# Single_cell_module.net
KiCad netlist of a schematic drawn in Altium Designer
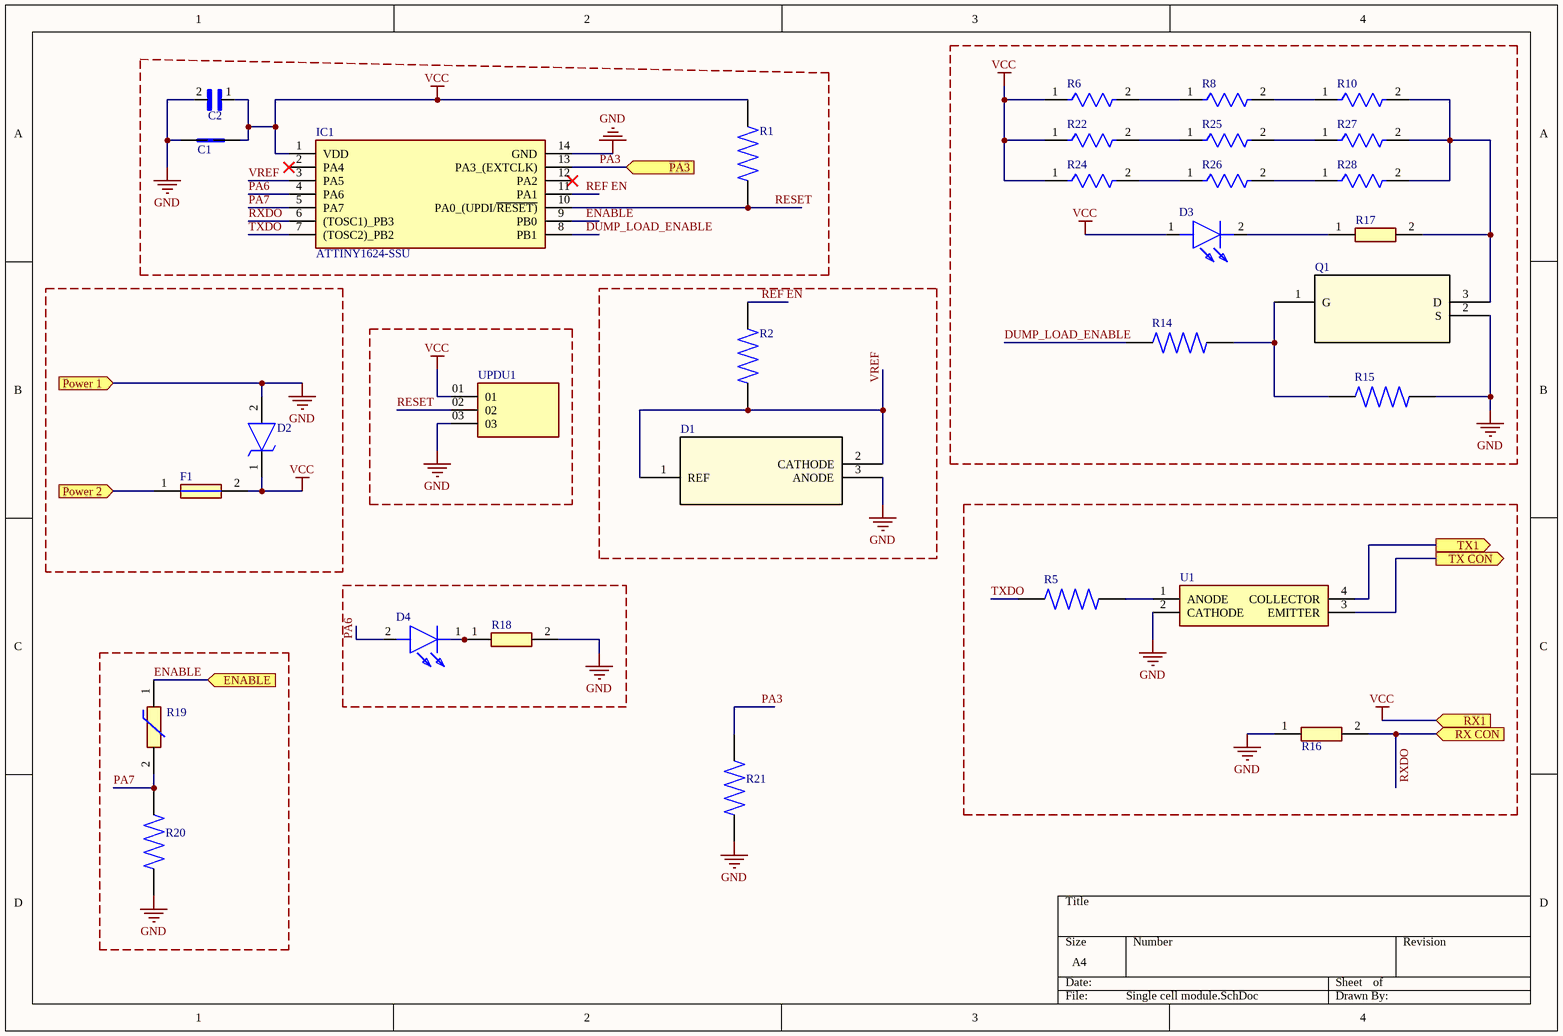
[diagram p0: Single cell module.SchDoc]

(export (version "E")
  (design (tool "Eeschema 10.0.6"))
  (components
    (comp (ref "C1")
      (value "CC0805KRX7R9BB104")
      (footprint "CAPC2012X70")
      (description "0.1ÂµF Â±10% 50V Ceramic Capacitor X7R 0805 _2012 Metric_")
      (fields (field (name "MF") "Yageo"))
      (libsource (lib "CC0805KRX7R9BB104") (part "CC0805KRX7R9BB104"))
    )
    (comp (ref "C2")
      (value "CL21A106KAYNNNE")
      (footprint "CAPC2012X135N")
      (description "10ÂµF Â±10% 25V Ceramic Capacitor X5R 0805 (2012 Metric)")
      (fields (field (name "MF") "Samsung") (field (name "DIGI-KEY_PART_NUMBER") "1276-2891-1-ND"))
      (libsource (lib "CL21A106KAYNNNE") (part "CL21A106KAYNNNE"))
    )
    (comp (ref "D1")
      (value "AZ432ANTR-E1")
      (footprint "SOT-23_DIO")
      (description "No Description Available")
      (libsource (lib "AZ432ANTR-E1") (part "AZ432ANTR-E1"))
    )
    (comp (ref "D2")
      (value "SM6T6V8A")
      (footprint "SamacSys:DIOM5436X265N")
      (description "TVS Diode (Uni-directional)")
      (fields (field (name "MOUSER PART NUMBER") "511-SM6T6V8A"))
      (libsource (lib "*") (part "SM6T6V8A"))
    )
    (comp (ref "D3")
      (value "598-2105-107F")
      (footprint "SamacSys:5982105107F")
      (description "LED")
      (libsource (lib "*") (part "598-2105-107F"))
    )
    (comp (ref "D4")
      (value "19-217_GHC-YR1S2_3T")
      (footprint "SamacSys:LEDC1608X50N")
      (description "LED")
      (fields
        (field (name "MANUFACTURER_PART_NUMBER") "19-217/GHC-YR1S2/3T")
        (field (name "MOUSER PART NUMBER") "638-19217GHCYR1S23T")
      )
      (libsource (lib "*") (part "19-217_GHC-YR1S2_3T"))
    )
    (comp (ref "F1")
      (value "MF-MSMF150-2")
      (footprint "SamacSys:FUSC4632X85N")
      (description "Fuse")
      (fields (field (name "MOUSER PART NUMBER") "652-MF-MSMF150-2"))
      (libsource (lib "*") (part "MF-MSMF150-2"))
    )
    (comp (ref "IC1")
      (value "ATTINY1624-SSU")
      (footprint "SamacSys:SOIC127P600X175-14N")
      (description "Integrated Circuit")
      (fields (field (name "MOUSER PART NUMBER") "556-ATTINY1624-SSU"))
      (libsource (lib "*") (part "ATTINY1624-SSU"))
    )
    (comp (ref "Q1")
      (value "AO3400A")
      (footprint "SOT-23-3L_AOS")
      (description "No Description Available")
      (libsource (lib "AO3400A") (part "AO3400A"))
    )
    (comp (ref "R1")
      (value "ERA6ARW104V")
      (footprint "RES_ERA6ARW104V")
      (libsource (lib "ERA6ARW104V") (part "ERA6ARW104V"))
    )
    (comp (ref "R2")
      (value "ERJU06J102V")
      (footprint "RES_ERJU06J102V")
      (libsource (lib "ERJU06J102V") (part "ERJU06J102V"))
    )
    (comp (ref "R5")
      (value "ERJ6ENF1800V")
      (footprint "RES_ERJ6ENF1800V")
      (libsource (lib "ERJ6ENF1800V") (part "ERJ6ENF1800V"))
    )
    (comp (ref "R6")
      (value "RC2010JK-070RL")
      (footprint "FP-RC2010-0_65-IPC_C")
      (description "RES SMD 0 OHM JUMPER 3/4W 2010")
      (fields (field (name "TOLERANCE") "5%"))
      (libsource (lib "Altium Content Vault") (part "1029c3af85768c4190bb7ad29bc67b5"))
    )
    (comp (ref "R8")
      (value "RC2010JK-070RL")
      (footprint "FP-RC2010-0_65-IPC_C")
      (description "RES SMD 0 OHM JUMPER 3/4W 2010")
      (fields (field (name "TOLERANCE") "5%"))
      (libsource (lib "Altium Content Vault") (part "1029c3af85768c4190bb7ad29bc67b5"))
    )
    (comp (ref "R10")
      (value "RC2010JK-070RL")
      (footprint "FP-RC2010-0_65-IPC_C")
      (description "RES SMD 0 OHM JUMPER 3/4W 2010")
      (fields (field (name "TOLERANCE") "5%"))
      (libsource (lib "Altium Content Vault") (part "1029c3af85768c4190bb7ad29bc67b5"))
    )
    (comp (ref "R14")
      (value "RT1206DRD07510RL")
      (footprint "RESC3116X65N")
      (description "RES SMD 510 OHM 0.5% 1/8W 1206")
      (libsource (lib "RT1206DRD07510RL") (part "RT1206DRD07510RL"))
    )
    (comp (ref "R15")
      (value "ERJP06D1002V")
      (footprint "RES_ERJP06D1002V")
      (libsource (lib "ERJP06D1002V") (part "ERJP06D1002V"))
    )
    (comp (ref "R16")
      (value "0805W8F2201T5E")
      (footprint "SamacSys:RESC2013X65N")
      (description "Resistor")
      (fields (field (name "MOUSER PART NUMBER") "303-0805W8F2201T5E"))
      (libsource (lib "*") (part "0805W8F2201T5E"))
    )
    (comp (ref "R17")
      (value "0805W8F2201T5E")
      (footprint "SamacSys:RESC2013X65N")
      (description "Resistor")
      (fields (field (name "MOUSER PART NUMBER") "303-0805W8F2201T5E"))
      (libsource (lib "*") (part "0805W8F2201T5E"))
    )
    (comp (ref "R18")
      (value "0805W8F2201T5E")
      (footprint "SamacSys:RESC2013X65N")
      (description "Resistor")
      (fields (field (name "MOUSER PART NUMBER") "303-0805W8F2201T5E"))
      (libsource (lib "*") (part "0805W8F2201T5E"))
    )
    (comp (ref "R19")
      (value "NTCS0805E3104GMT")
      (footprint "SamacSys:THRMC2012X95N")
      (description "Thermistor")
      (fields (field (name "MOUSER PART NUMBER") "594-NTCS0805E3104GMT"))
      (libsource (lib "*") (part "NTCS0805E3104GMT"))
    )
    (comp (ref "R20")
      (value "ERJP06D1002V")
      (footprint "RES_ERJP06D1002V")
      (libsource (lib "ERJP06D1002V") (part "ERJP06D1002V"))
    )
    (comp (ref "R21")
      (value "ERJP06D1002V")
      (footprint "RES_ERJP06D1002V")
      (libsource (lib "ERJP06D1002V") (part "ERJP06D1002V"))
    )
    (comp (ref "R22")
      (value "RC2010JK-070RL")
      (footprint "FP-RC2010-0_65-IPC_C")
      (description "RES SMD 0 OHM JUMPER 3/4W 2010")
      (fields (field (name "TOLERANCE") "5%"))
      (libsource (lib "Altium Content Vault") (part "1029c3af85768c4190bb7ad29bc67b5"))
    )
    (comp (ref "R24")
      (value "RC2010JK-070RL")
      (footprint "FP-RC2010-0_65-IPC_C")
      (description "RES SMD 0 OHM JUMPER 3/4W 2010")
      (fields (field (name "TOLERANCE") "5%"))
      (libsource (lib "Altium Content Vault") (part "1029c3af85768c4190bb7ad29bc67b5"))
    )
    (comp (ref "R25")
      (value "RC2010JK-070RL")
      (footprint "FP-RC2010-0_65-IPC_C")
      (description "RES SMD 0 OHM JUMPER 3/4W 2010")
      (fields (field (name "TOLERANCE") "5%"))
      (libsource (lib "Altium Content Vault") (part "1029c3af85768c4190bb7ad29bc67b5"))
    )
    (comp (ref "R26")
      (value "RC2010JK-070RL")
      (footprint "FP-RC2010-0_65-IPC_C")
      (description "RES SMD 0 OHM JUMPER 3/4W 2010")
      (fields (field (name "TOLERANCE") "5%"))
      (libsource (lib "Altium Content Vault") (part "1029c3af85768c4190bb7ad29bc67b5"))
    )
    (comp (ref "R27")
      (value "RC2010JK-070RL")
      (footprint "FP-RC2010-0_65-IPC_C")
      (description "RES SMD 0 OHM JUMPER 3/4W 2010")
      (fields (field (name "TOLERANCE") "5%"))
      (libsource (lib "Altium Content Vault") (part "1029c3af85768c4190bb7ad29bc67b5"))
    )
    (comp (ref "R28")
      (value "RC2010JK-070RL")
      (footprint "FP-RC2010-0_65-IPC_C")
      (description "RES SMD 0 OHM JUMPER 3/4W 2010")
      (fields (field (name "TOLERANCE") "5%"))
      (libsource (lib "Altium Content Vault") (part "1029c3af85768c4190bb7ad29bc67b5"))
    )
    (comp (ref "U1")
      (value "EL3H7_B__TA_-G")
      (footprint "SamacSys:SOIC127P700X200-4N")
      (description "Integrated Circuit")
      (fields
        (field (name "MANUFACTURER_PART_NUMBER") "EL3H7(B)(TA)-G")
        (field (name "MOUSER PART NUMBER") "638-EL3H7BTAG")
      )
      (libsource (lib "*") (part "EL3H7_B__TA_-G"))
    )
    (comp (ref "UPDU1")
      (value "TS-103-T-A-1")
      (footprint "SAMTEC_TS-103-T-A-1")
      (description "Connector Header position")
      (fields (field (name "MF") "Samtec"))
      (libsource (lib "TS-103-T-A-1") (part "TS-103-T-A-1"))
    )
  )
  (nets
    (net (code "1") (name "/DUMP_LOAD_ENABLE") (class "Default")
      (node (ref "IC1") (pin "8") (pinfunction "PB1_8") (pintype "passive"))
      (node (ref "R14") (pin "1") (pinfunction "1_1") (pintype "passive"))
    )
    (net (code "2") (name "/ENABLE") (class "Default")
      (node (ref "IC1") (pin "9") (pinfunction "PB0_9") (pintype "passive"))
      (node (ref "R19") (pin "1") (pinfunction "1_1") (pintype "passive"))
    )
    (net (code "3") (name "/PA3") (class "Default")
      (node (ref "IC1") (pin "13") (pinfunction "PA3_(EXTCLK)_13") (pintype "passive"))
      (node (ref "R21") (pin "2") (pinfunction "2_2") (pintype "passive"))
    )
    (net (code "4") (name "/PA6") (class "Default")
      (node (ref "D4") (pin "2") (pinfunction "A_2") (pintype "passive"))
      (node (ref "IC1") (pin "4") (pinfunction "PA6_4") (pintype "passive"))
    )
    (net (code "5") (name "/PA7") (class "Default")
      (node (ref "IC1") (pin "5") (pinfunction "PA7_5") (pintype "passive"))
      (node (ref "R19") (pin "2") (pinfunction "2_2") (pintype "passive"))
      (node (ref "R20") (pin "2") (pinfunction "2_2") (pintype "passive"))
    )
    (net (code "6") (name "/Power 2") (class "Default")
      (node (ref "F1") (pin "1") (pinfunction "1_1") (pintype "passive"))
    )
    (net (code "7") (name "/REF EN") (class "Default")
      (node (ref "IC1") (pin "11") (pinfunction "PA1_11") (pintype "passive"))
      (node (ref "R2") (pin "2") (pinfunction "2_2") (pintype "passive"))
    )
    (net (code "8") (name "/RESET") (class "Default")
      (node (ref "IC1") (pin "10") (pinfunction "PA0_(UPDI/~{RESET)}_10") (pintype "passive"))
      (node (ref "R1") (pin "1") (pinfunction "1_1") (pintype "passive"))
      (node (ref "UPDU1") (pin "02") (pinfunction "02_02") (pintype "passive"))
    )
    (net (code "9") (name "/RXDO") (class "Default")
      (node (ref "IC1") (pin "6") (pinfunction "(TOSC1)_PB3_6") (pintype "passive"))
      (node (ref "R16") (pin "2") (pinfunction "2_2") (pintype "passive"))
    )
    (net (code "10") (name "/TX CON") (class "Default")
      (node (ref "U1") (pin "3") (pinfunction "EMITTER_3") (pintype "passive"))
    )
    (net (code "11") (name "/TX1") (class "Default")
      (node (ref "U1") (pin "4") (pinfunction "COLLECTOR_4") (pintype "passive"))
    )
    (net (code "12") (name "/TXDO") (class "Default")
      (node (ref "IC1") (pin "7") (pinfunction "(TOSC2)_PB2_7") (pintype "passive"))
      (node (ref "R5") (pin "1") (pinfunction "1_1") (pintype "passive"))
    )
    (net (code "13") (name "/VREF") (class "Default")
      (node (ref "D1") (pin "1") (pinfunction "REF_1") (pintype "passive"))
      (node (ref "D1") (pin "2") (pinfunction "CATHODE_2") (pintype "passive"))
      (node (ref "IC1") (pin "3") (pinfunction "PA5_3") (pintype "passive"))
      (node (ref "R2") (pin "1") (pinfunction "1_1") (pintype "passive"))
    )
    (net (code "14") (name "GND") (class "Default")
      (node (ref "C1") (pin "1") (pinfunction "1_1") (pintype "passive"))
      (node (ref "C2") (pin "2") (pinfunction "2_2") (pintype "passive"))
      (node (ref "D1") (pin "3") (pinfunction "ANODE_3") (pintype "passive"))
      (node (ref "D2") (pin "2") (pinfunction "A_2") (pintype "passive"))
      (node (ref "IC1") (pin "14") (pinfunction "GND_14") (pintype "passive"))
      (node (ref "Q1") (pin "2") (pinfunction "S_2") (pintype "passive"))
      (node (ref "R15") (pin "2") (pinfunction "2_2") (pintype "passive"))
      (node (ref "R16") (pin "1") (pinfunction "1_1") (pintype "passive"))
      (node (ref "R18") (pin "2") (pinfunction "2_2") (pintype "passive"))
      (node (ref "R20") (pin "1") (pinfunction "1_1") (pintype "passive"))
      (node (ref "R21") (pin "1") (pinfunction "1_1") (pintype "passive"))
      (node (ref "U1") (pin "2") (pinfunction "CATHODE_2") (pintype "passive"))
      (node (ref "UPDU1") (pin "03") (pinfunction "03_03") (pintype "passive"))
    )
    (net (code "15") (name "Net-(D3-K)") (class "Default")
      (node (ref "D3") (pin "2") (pinfunction "K_2") (pintype "passive"))
      (node (ref "R17") (pin "1") (pinfunction "1_1") (pintype "passive"))
    )
    (net (code "16") (name "Net-(D4-K)") (class "Default")
      (node (ref "D4") (pin "1") (pinfunction "K_1") (pintype "passive"))
      (node (ref "R18") (pin "1") (pinfunction "1_1") (pintype "passive"))
    )
    (net (code "17") (name "Net-(Q1-D)") (class "Default")
      (node (ref "Q1") (pin "3") (pinfunction "D_3") (pintype "passive"))
      (node (ref "R10") (pin "2") (pinfunction "2_2") (pintype "passive"))
      (node (ref "R17") (pin "2") (pinfunction "2_2") (pintype "passive"))
      (node (ref "R27") (pin "2") (pinfunction "2_2") (pintype "passive"))
      (node (ref "R28") (pin "2") (pinfunction "2_2") (pintype "passive"))
    )
    (net (code "18") (name "Net-(Q1-G)") (class "Default")
      (node (ref "Q1") (pin "1") (pinfunction "G_1") (pintype "passive"))
      (node (ref "R14") (pin "2") (pinfunction "2_2") (pintype "passive"))
      (node (ref "R15") (pin "1") (pinfunction "1_1") (pintype "passive"))
    )
    (net (code "19") (name "Net-(R6-Pad2)") (class "Default")
      (node (ref "R6") (pin "2") (pinfunction "2_2") (pintype "passive"))
      (node (ref "R8") (pin "1") (pinfunction "1_1") (pintype "passive"))
    )
    (net (code "20") (name "Net-(R10-Pad1)") (class "Default")
      (node (ref "R10") (pin "1") (pinfunction "1_1") (pintype "passive"))
      (node (ref "R8") (pin "2") (pinfunction "2_2") (pintype "passive"))
    )
    (net (code "21") (name "Net-(R22-Pad2)") (class "Default")
      (node (ref "R22") (pin "2") (pinfunction "2_2") (pintype "passive"))
      (node (ref "R25") (pin "1") (pinfunction "1_1") (pintype "passive"))
    )
    (net (code "22") (name "Net-(R24-Pad2)") (class "Default")
      (node (ref "R24") (pin "2") (pinfunction "2_2") (pintype "passive"))
      (node (ref "R26") (pin "1") (pinfunction "1_1") (pintype "passive"))
    )
    (net (code "23") (name "Net-(R25-Pad2)") (class "Default")
      (node (ref "R25") (pin "2") (pinfunction "2_2") (pintype "passive"))
      (node (ref "R27") (pin "1") (pinfunction "1_1") (pintype "passive"))
    )
    (net (code "24") (name "Net-(R26-Pad2)") (class "Default")
      (node (ref "R26") (pin "2") (pinfunction "2_2") (pintype "passive"))
      (node (ref "R28") (pin "1") (pinfunction "1_1") (pintype "passive"))
    )
    (net (code "25") (name "Net-(U1-ANODE)") (class "Default")
      (node (ref "R5") (pin "2") (pinfunction "2_2") (pintype "passive"))
      (node (ref "U1") (pin "1") (pinfunction "ANODE_1") (pintype "passive"))
    )
    (net (code "26") (name "VCC") (class "Default")
      (node (ref "C1") (pin "2") (pinfunction "2_2") (pintype "passive"))
      (node (ref "C2") (pin "1") (pinfunction "1_1") (pintype "passive"))
      (node (ref "D2") (pin "1") (pinfunction "K_1") (pintype "passive"))
      (node (ref "D3") (pin "1") (pinfunction "A_1") (pintype "passive"))
      (node (ref "F1") (pin "2") (pinfunction "2_2") (pintype "passive"))
      (node (ref "IC1") (pin "1") (pinfunction "VDD_1") (pintype "passive"))
      (node (ref "R1") (pin "2") (pinfunction "2_2") (pintype "passive"))
      (node (ref "R22") (pin "1") (pinfunction "1_1") (pintype "passive"))
      (node (ref "R24") (pin "1") (pinfunction "1_1") (pintype "passive"))
      (node (ref "R6") (pin "1") (pinfunction "1_1") (pintype "passive"))
      (node (ref "UPDU1") (pin "01") (pinfunction "01_01") (pintype "passive"))
    )
    (net (code "27") (name "unconnected-(IC1-PA2-Pad12)") (class "Default")
      (node (ref "IC1") (pin "12") (pinfunction "PA2_12") (pintype "passive+no_connect"))
    )
    (net (code "28") (name "unconnected-(IC1-PA4-Pad2)") (class "Default")
      (node (ref "IC1") (pin "2") (pinfunction "PA4_2") (pintype "passive+no_connect"))
    )
  )
)
